# SphereFreezerMonitor.net
KiCad netlist of a schematic drawn in EAGLE
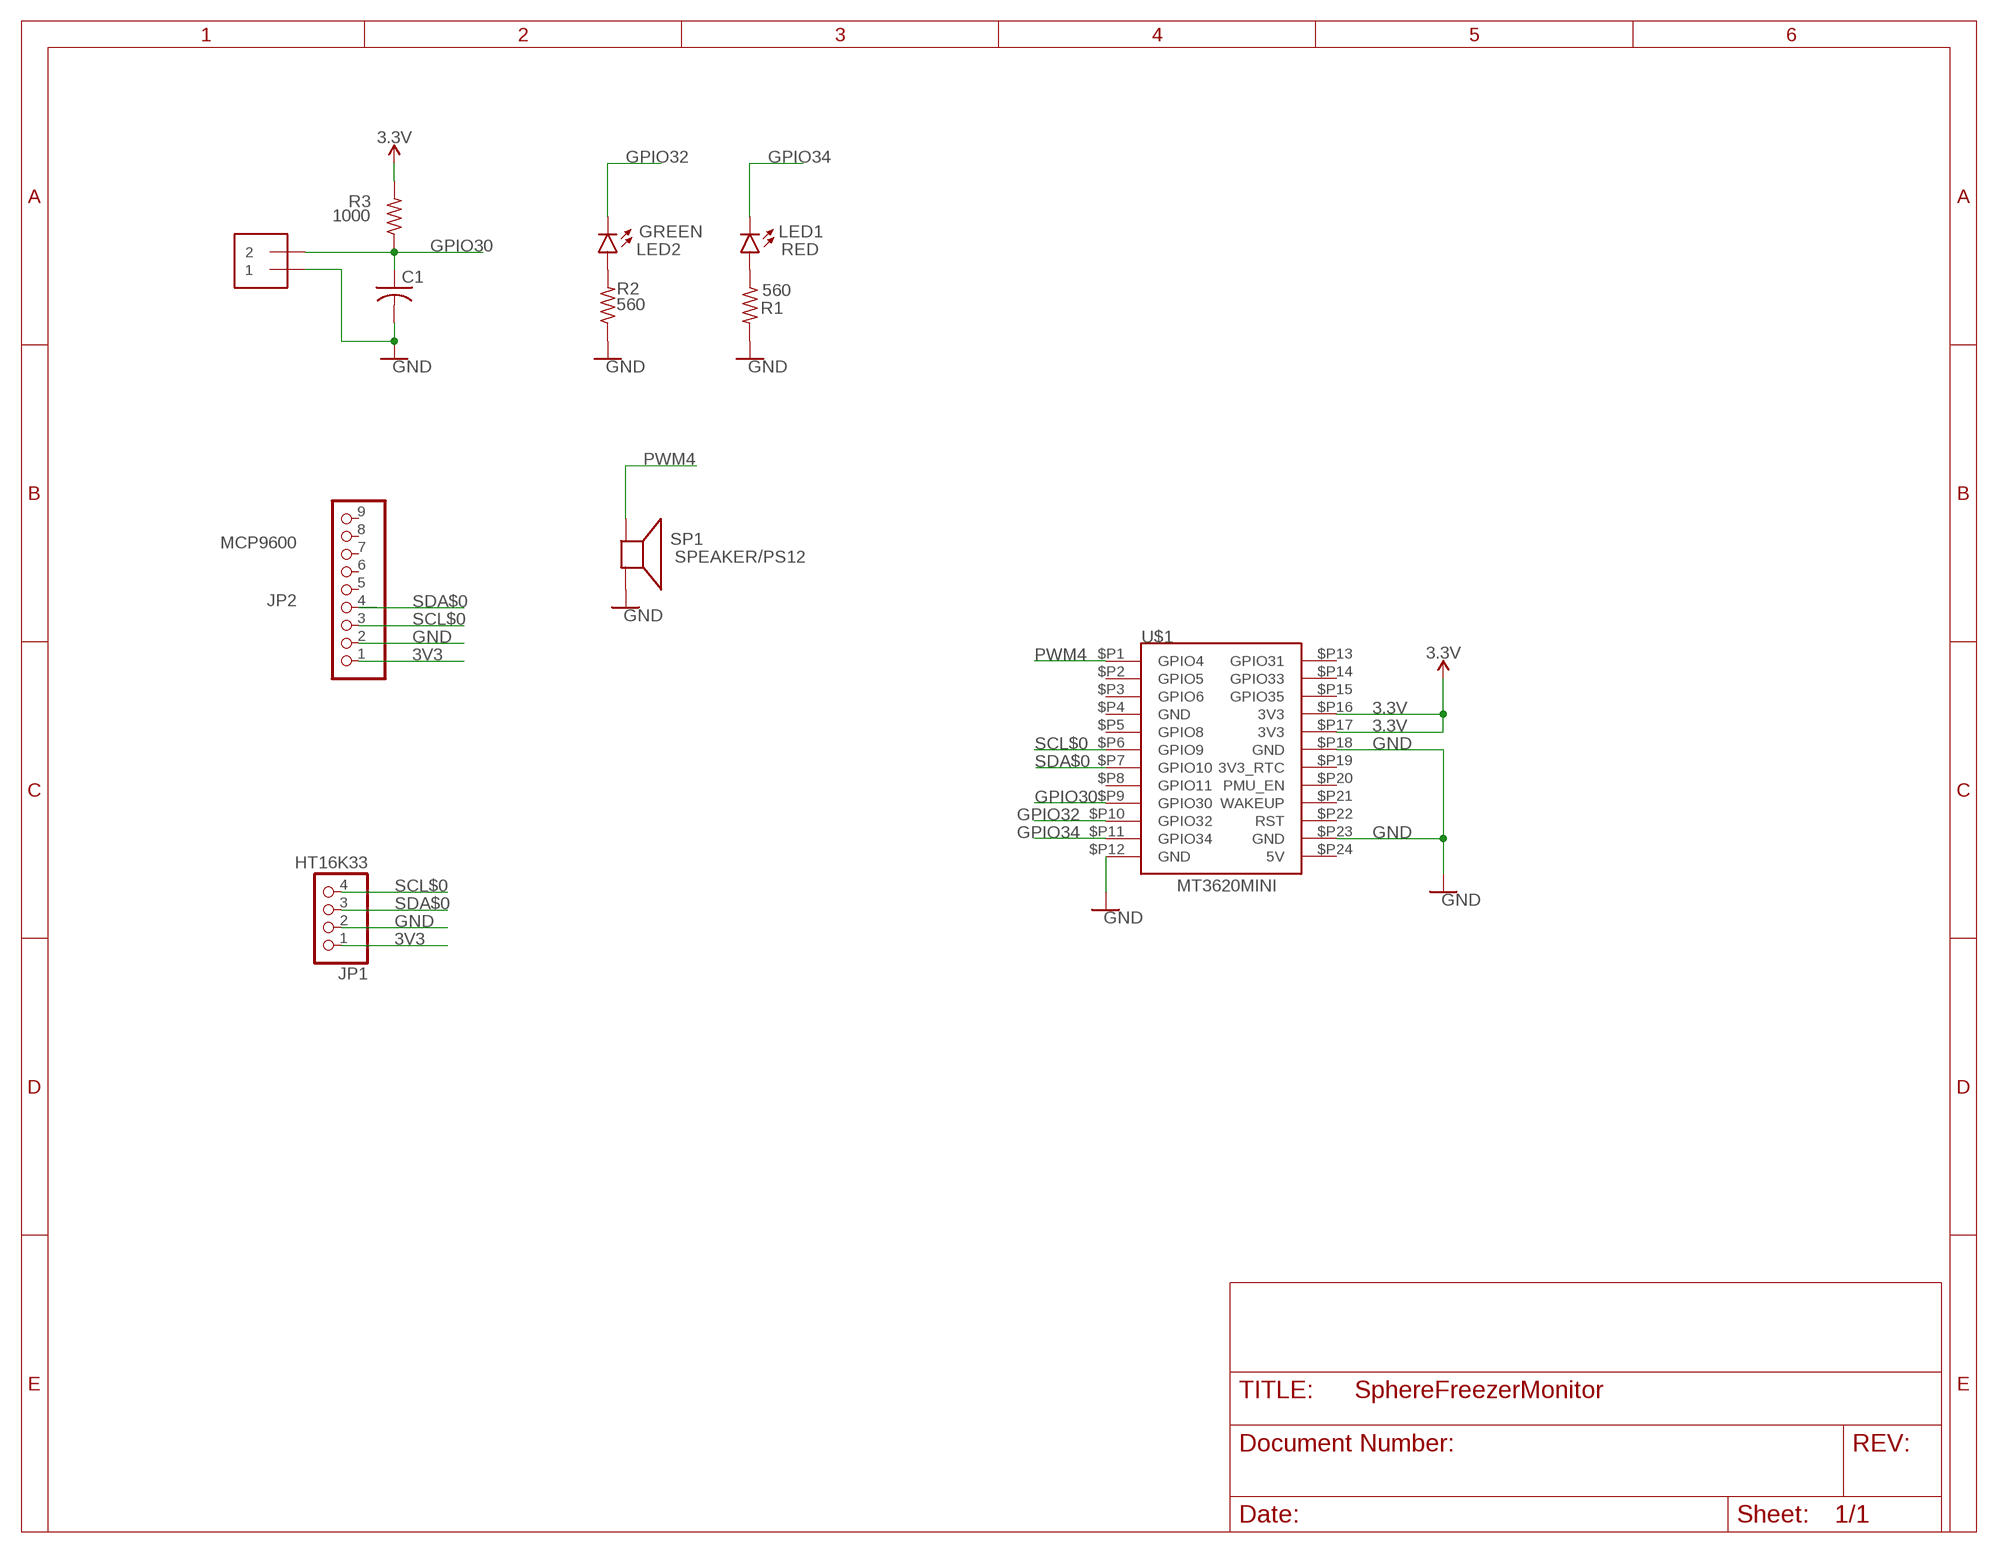
[diagram p0: schematic, sheet 1]

(export (version "E")
  (design (tool "Eeschema 10.0.6"))
  (components
    (comp (ref "C1")
      (value "C-US025-025X050")
      (footprint "eagle-import:C025-025X050")
      (libsource (lib "eagle-import") (part "C-US025-025X050"))
    )
    (comp (ref "J1")
      (value "1X2-3.5MM")
      (footprint "eagle-import:1X2-3.5MM")
      (libsource (lib "eagle-import") (part "1X2-3.5MM"))
    )
    (comp (ref "JP1")
      (value "HT16K33")
      (footprint "eagle-import:1X04")
      (libsource (lib "eagle-import") (part "PINHD-1X4"))
    )
    (comp (ref "JP2")
      (value "MCP9600")
      (footprint "eagle-import:1X09")
      (libsource (lib "eagle-import") (part "PINHD-1X9"))
    )
    (comp (ref "LED1")
      (value "RED")
      (footprint "eagle-import:LED10MM")
      (libsource (lib "eagle-import") (part "LED10MM"))
    )
    (comp (ref "LED2")
      (value "GREEN")
      (footprint "eagle-import:LED10MM")
      (libsource (lib "eagle-import") (part "LED10MM"))
    )
    (comp (ref "R1")
      (value "560")
      (footprint "eagle-import:0207_9")
      (libsource (lib "eagle-import") (part "R-US_0207/9"))
    )
    (comp (ref "R2")
      (value "560")
      (footprint "eagle-import:0207_9")
      (libsource (lib "eagle-import") (part "R-US_0207/9"))
    )
    (comp (ref "R3")
      (value "1000")
      (footprint "eagle-import:0207_9")
      (libsource (lib "eagle-import") (part "R-US_0207/9"))
    )
    (comp (ref "SP1")
      (value "SPEAKER/PS12")
      (footprint "eagle-import:PS12")
      (libsource (lib "eagle-import") (part "SPEAKER/PS12"))
    )
    (comp (ref "U$1")
      (value "MT3620MINI")
      (footprint "eagle-import:MT3620MINI")
      (libsource (lib "eagle-import") (part "MT3620MINI"))
    )
  )
  (nets
    (net (code "1") (name "/3V3") (class "Default")
      (node (ref "JP1") (pin "1") (pinfunction "1_1") (pintype "passive"))
      (node (ref "JP2") (pin "1") (pinfunction "1_1") (pintype "passive"))
    )
    (net (code "2") (name "/3V3_RTC") (class "Default")
      (node (ref "U$1") (pin "$P19") (pinfunction "3V3_RTC_$P19") (pintype "power_in"))
    )
    (net (code "3") (name "/GPIO30") (class "Default")
      (node (ref "C1") (pin "1") (pinfunction "1_1") (pintype "passive"))
      (node (ref "J1") (pin "2") (pinfunction "2_2") (pintype "passive"))
      (node (ref "R3") (pin "1") (pinfunction "1_1") (pintype "passive"))
      (node (ref "U$1") (pin "$P9") (pinfunction "GPIO30_$P9") (pintype "bidirectional"))
    )
    (net (code "4") (name "/GPIO32") (class "Default")
      (node (ref "LED2") (pin "K") (pinfunction "C_K") (pintype "passive"))
      (node (ref "U$1") (pin "$P10") (pinfunction "GPIO32_$P10") (pintype "bidirectional"))
    )
    (net (code "5") (name "/GPIO34") (class "Default")
      (node (ref "LED1") (pin "K") (pinfunction "C_K") (pintype "passive"))
      (node (ref "U$1") (pin "$P11") (pinfunction "GPIO34_$P11") (pintype "bidirectional"))
    )
    (net (code "6") (name "/PWM4") (class "Default")
      (node (ref "SP1") (pin "P$1") (pinfunction "+_P$1") (pintype "passive"))
      (node (ref "U$1") (pin "$P1") (pinfunction "GPIO4_$P1") (pintype "bidirectional"))
    )
    (net (code "7") (name "/SCL$0") (class "Default")
      (node (ref "JP1") (pin "4") (pinfunction "4_4") (pintype "passive"))
      (node (ref "JP2") (pin "3") (pinfunction "3_3") (pintype "passive"))
      (node (ref "U$1") (pin "$P6") (pinfunction "GPIO9_$P6") (pintype "bidirectional"))
    )
    (net (code "8") (name "/SDA$0") (class "Default")
      (node (ref "JP1") (pin "3") (pinfunction "3_3") (pintype "passive"))
      (node (ref "JP2") (pin "4") (pinfunction "4_4") (pintype "passive"))
      (node (ref "U$1") (pin "$P7") (pinfunction "GPIO10_$P7") (pintype "bidirectional"))
    )
    (net (code "9") (name "3.3V") (class "Default")
      (node (ref "R3") (pin "2") (pinfunction "2_2") (pintype "passive"))
      (node (ref "U$1") (pin "$P16") (pinfunction "3V3_$P16") (pintype "power_in"))
      (node (ref "U$1") (pin "$P17") (pinfunction "3V3_$P17") (pintype "power_in"))
    )
    (net (code "10") (name "GND") (class "Default")
      (node (ref "C1") (pin "2") (pinfunction "2_2") (pintype "passive"))
      (node (ref "J1") (pin "1") (pinfunction "1_1") (pintype "passive"))
      (node (ref "JP1") (pin "2") (pinfunction "2_2") (pintype "passive"))
      (node (ref "JP2") (pin "2") (pinfunction "2_2") (pintype "passive"))
      (node (ref "R1") (pin "2") (pinfunction "2_2") (pintype "passive"))
      (node (ref "R2") (pin "1") (pinfunction "1_1") (pintype "passive"))
      (node (ref "SP1") (pin "P$2") (pinfunction "-_P$2") (pintype "passive"))
      (node (ref "U$1") (pin "$P12") (pinfunction "GND_$P12") (pintype "bidirectional"))
      (node (ref "U$1") (pin "$P18") (pinfunction "GND_$P18") (pintype "bidirectional"))
      (node (ref "U$1") (pin "$P23") (pinfunction "GND_$P23") (pintype "bidirectional"))
    )
    (net (code "11") (name "Net-(LED1-PadA)") (class "Default")
      (node (ref "LED1") (pin "A") (pinfunction "A_A") (pintype "passive"))
      (node (ref "R1") (pin "1") (pinfunction "1_1") (pintype "passive"))
    )
    (net (code "12") (name "Net-(LED2-PadA)") (class "Default")
      (node (ref "LED2") (pin "A") (pinfunction "A_A") (pintype "passive"))
      (node (ref "R2") (pin "2") (pinfunction "2_2") (pintype "passive"))
    )
    (net (code "13") (name "unconnected-(JP2-Pad5)") (class "Default")
      (node (ref "JP2") (pin "5") (pinfunction "5_5") (pintype "passive"))
    )
    (net (code "14") (name "unconnected-(JP2-Pad6)") (class "Default")
      (node (ref "JP2") (pin "6") (pinfunction "6_6") (pintype "passive"))
    )
    (net (code "15") (name "unconnected-(JP2-Pad7)") (class "Default")
      (node (ref "JP2") (pin "7") (pinfunction "7_7") (pintype "passive"))
    )
    (net (code "16") (name "unconnected-(JP2-Pad8)") (class "Default")
      (node (ref "JP2") (pin "8") (pinfunction "8_8") (pintype "passive"))
    )
    (net (code "17") (name "unconnected-(JP2-Pad9)") (class "Default")
      (node (ref "JP2") (pin "9") (pinfunction "9_9") (pintype "passive"))
    )
    (net (code "18") (name "unconnected-(U$1-5V-Pad$P24)") (class "Default")
      (node (ref "U$1") (pin "$P24") (pinfunction "5V_$P24") (pintype "bidirectional"))
    )
    (net (code "19") (name "unconnected-(U$1-GND-Pad$P4)") (class "Default")
      (node (ref "U$1") (pin "$P4") (pinfunction "GND_$P4") (pintype "bidirectional"))
    )
    (net (code "20") (name "unconnected-(U$1-GPIO5-Pad$P2)") (class "Default")
      (node (ref "U$1") (pin "$P2") (pinfunction "GPIO5_$P2") (pintype "bidirectional"))
    )
    (net (code "21") (name "unconnected-(U$1-GPIO6-Pad$P3)") (class "Default")
      (node (ref "U$1") (pin "$P3") (pinfunction "GPIO6_$P3") (pintype "bidirectional"))
    )
    (net (code "22") (name "unconnected-(U$1-GPIO8-Pad$P5)") (class "Default")
      (node (ref "U$1") (pin "$P5") (pinfunction "GPIO8_$P5") (pintype "bidirectional"))
    )
    (net (code "23") (name "unconnected-(U$1-GPIO11-Pad$P8)") (class "Default")
      (node (ref "U$1") (pin "$P8") (pinfunction "GPIO11_$P8") (pintype "bidirectional"))
    )
    (net (code "24") (name "unconnected-(U$1-GPIO31-Pad$P13)") (class "Default")
      (node (ref "U$1") (pin "$P13") (pinfunction "GPIO31_$P13") (pintype "bidirectional"))
    )
    (net (code "25") (name "unconnected-(U$1-GPIO33-Pad$P14)") (class "Default")
      (node (ref "U$1") (pin "$P14") (pinfunction "GPIO33_$P14") (pintype "bidirectional"))
    )
    (net (code "26") (name "unconnected-(U$1-GPIO35-Pad$P15)") (class "Default")
      (node (ref "U$1") (pin "$P15") (pinfunction "GPIO35_$P15") (pintype "bidirectional"))
    )
    (net (code "27") (name "unconnected-(U$1-PMU_EN-Pad$P20)") (class "Default")
      (node (ref "U$1") (pin "$P20") (pinfunction "PMU_EN_$P20") (pintype "bidirectional"))
    )
    (net (code "28") (name "unconnected-(U$1-RST-Pad$P22)") (class "Default")
      (node (ref "U$1") (pin "$P22") (pinfunction "RST_$P22") (pintype "bidirectional"))
    )
    (net (code "29") (name "unconnected-(U$1-WAKEUP-Pad$P21)") (class "Default")
      (node (ref "U$1") (pin "$P21") (pinfunction "WAKEUP_$P21") (pintype "bidirectional"))
    )
  )
)
